# HDMI.net
KiCad netlist of a schematic drawn in Altium Designer
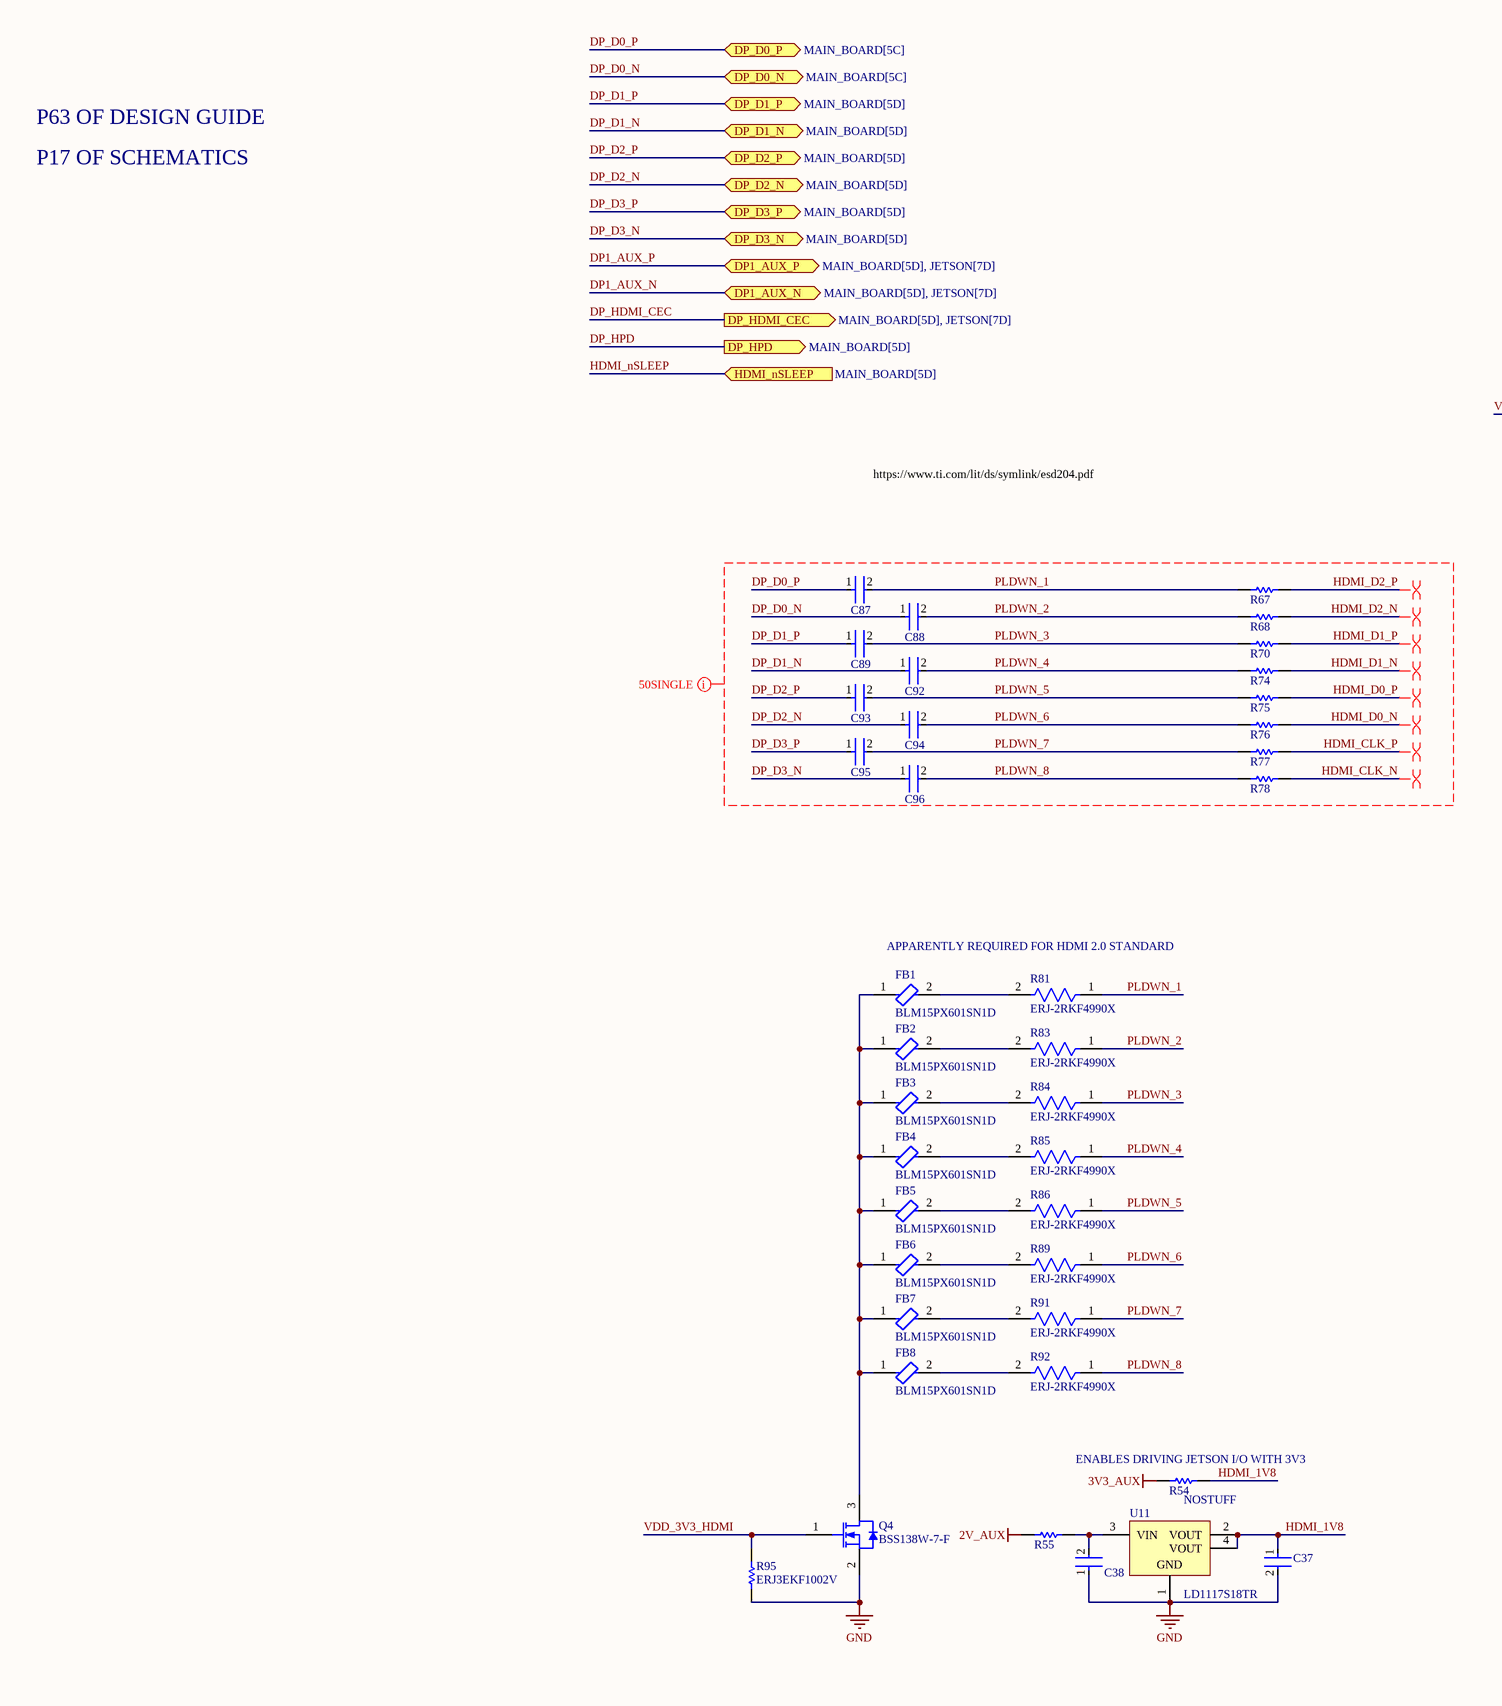
[diagram p0: HDMI.SchDoc, left]
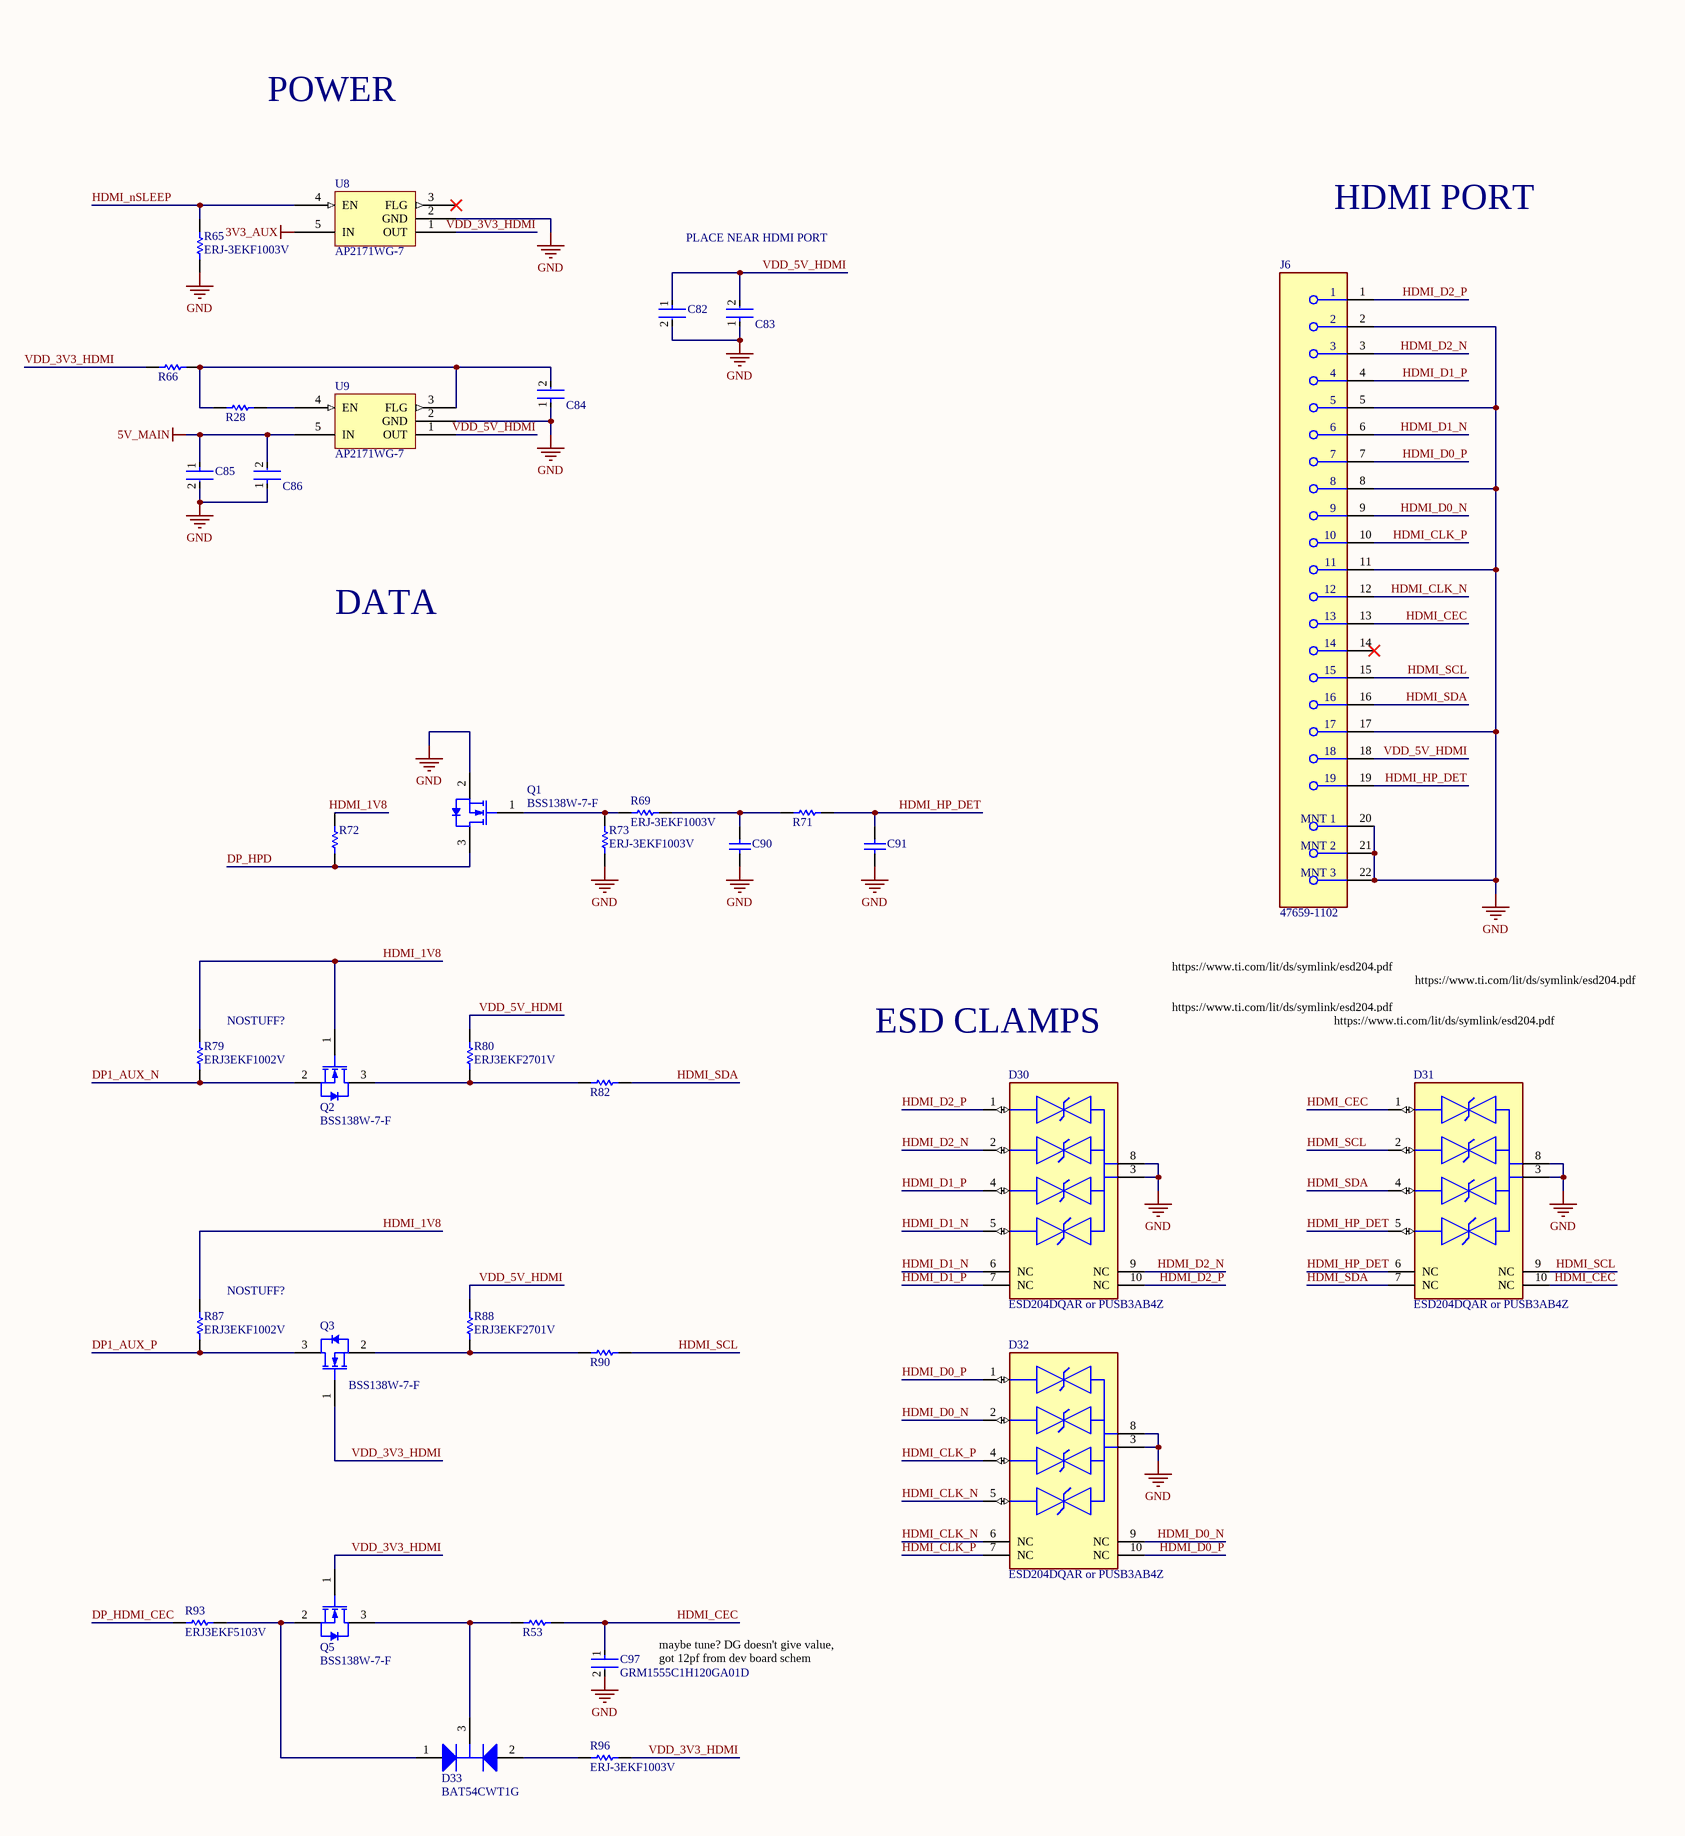
[diagram p1: HDMI.SchDoc, right]

(export (version "E")
  (design (tool "Eeschema 10.0.6"))
  (components
    (comp (ref "C37")
      (value "GRM188R60J106ME47D")
      (footprint "FP-GRM188-0_1-e0_2_0_55-IPC_A")
      (description "Chip Multilayer Ceramic Capacitors for General Purpose, 0603, 10uF, X5R, 15%, 20%, 6.3V")
      (fields (field (name "VOLTAGE") "6.3V") (field (name "TOLERANCE") "20%"))
      (libsource (lib "Altium Content Vault") (part "02cd4be3c70576c341d710602a673aa"))
    )
    (comp (ref "C38")
      (value "C1005X7R1H104K050BB")
      (footprint "FP-C1005-050-0_05-IPC_C")
      (description "Multilayer Ceramic Capacitors 100nF ±10% 50V X7R SMD 0402")
      (fields (field (name "VOLTAGE") "50V") (field (name "TOLERANCE") "10%"))
      (libsource (lib "Altium Content Vault") (part "b4654b650e69147ec39a6b967a45e02"))
    )
    (comp (ref "C82")
      (value "GRM188R60J106ME47D")
      (footprint "FP-GRM188-0_1-e0_2_0_55-IPC_A")
      (description "Chip Multilayer Ceramic Capacitors for General Purpose, 0603, 10uF, X5R, 15%, 20%, 6.3V")
      (fields (field (name "VOLTAGE") "6.3V") (field (name "TOLERANCE") "20%"))
      (libsource (lib "Altium Content Vault") (part "02cd4be3c70576c341d710602a673aa"))
    )
    (comp (ref "C83")
      (value "C1005X7R1H104K050BB")
      (footprint "FP-C1005-050-0_05-IPC_C")
      (description "Multilayer Ceramic Capacitors 100nF ±10% 50V X7R SMD 0402")
      (fields (field (name "VOLTAGE") "50V") (field (name "TOLERANCE") "10%"))
      (libsource (lib "Altium Content Vault") (part "b4654b650e69147ec39a6b967a45e02"))
    )
    (comp (ref "C84")
      (value "C1005X7R1H104K050BB")
      (footprint "FP-C1005-050-0_05-IPC_C")
      (description "Multilayer Ceramic Capacitors 100nF ±10% 50V X7R SMD 0402")
      (fields (field (name "VOLTAGE") "50V") (field (name "TOLERANCE") "10%"))
      (libsource (lib "Altium Content Vault") (part "b4654b650e69147ec39a6b967a45e02"))
    )
    (comp (ref "C85")
      (value "GRM188R60J106ME47D")
      (footprint "FP-GRM188-0_1-e0_2_0_55-IPC_A")
      (description "Chip Multilayer Ceramic Capacitors for General Purpose, 0603, 10uF, X5R, 15%, 20%, 6.3V")
      (fields (field (name "VOLTAGE") "6.3V") (field (name "TOLERANCE") "20%"))
      (libsource (lib "Altium Content Vault") (part "02cd4be3c70576c341d710602a673aa"))
    )
    (comp (ref "C86")
      (value "C1005X7R1H104K050BB")
      (footprint "FP-C1005-050-0_05-IPC_C")
      (description "Multilayer Ceramic Capacitors 100nF ±10% 50V X7R SMD 0402")
      (fields (field (name "VOLTAGE") "50V") (field (name "TOLERANCE") "10%"))
      (libsource (lib "Altium Content Vault") (part "b4654b650e69147ec39a6b967a45e02"))
    )
    (comp (ref "C87")
      (value "C1005X7R1H104K050BB")
      (footprint "FP-C1005-050-0_05-IPC_C")
      (description "Multilayer Ceramic Capacitors 100nF ±10% 50V X7R SMD 0402")
      (fields (field (name "VOLTAGE") "50V") (field (name "TOLERANCE") "10%"))
      (libsource (lib "Altium Content Vault") (part "b4654b650e69147ec39a6b967a45e02"))
    )
    (comp (ref "C88")
      (value "C1005X7R1H104K050BB")
      (footprint "FP-C1005-050-0_05-IPC_C")
      (description "Multilayer Ceramic Capacitors 100nF ±10% 50V X7R SMD 0402")
      (fields (field (name "VOLTAGE") "50V") (field (name "TOLERANCE") "10%"))
      (libsource (lib "Altium Content Vault") (part "b4654b650e69147ec39a6b967a45e02"))
    )
    (comp (ref "C89")
      (value "C1005X7R1H104K050BB")
      (footprint "FP-C1005-050-0_05-IPC_C")
      (description "Multilayer Ceramic Capacitors 100nF ±10% 50V X7R SMD 0402")
      (fields (field (name "VOLTAGE") "50V") (field (name "TOLERANCE") "10%"))
      (libsource (lib "Altium Content Vault") (part "b4654b650e69147ec39a6b967a45e02"))
    )
    (comp (ref "C90")
      (value "C0402C221K5RAC7867")
      (footprint "CAPC1005X60X30NL05T10")
      (fields (field (name "MANUFACTURER") "Kemet"))
      (libsource (lib "Altium Content Vault") (part "CAP"))
    )
    (comp (ref "C91")
      (value "C0402C221K5RAC7867")
      (footprint "CAPC1005X60X30NL05T10")
      (fields (field (name "MANUFACTURER") "Kemet"))
      (libsource (lib "Altium Content Vault") (part "CAP"))
    )
    (comp (ref "C92")
      (value "C1005X7R1H104K050BB")
      (footprint "FP-C1005-050-0_05-IPC_C")
      (description "Multilayer Ceramic Capacitors 100nF ±10% 50V X7R SMD 0402")
      (fields (field (name "VOLTAGE") "50V") (field (name "TOLERANCE") "10%"))
      (libsource (lib "Altium Content Vault") (part "b4654b650e69147ec39a6b967a45e02"))
    )
    (comp (ref "C93")
      (value "C1005X7R1H104K050BB")
      (footprint "FP-C1005-050-0_05-IPC_C")
      (description "Multilayer Ceramic Capacitors 100nF ±10% 50V X7R SMD 0402")
      (fields (field (name "VOLTAGE") "50V") (field (name "TOLERANCE") "10%"))
      (libsource (lib "Altium Content Vault") (part "b4654b650e69147ec39a6b967a45e02"))
    )
    (comp (ref "C94")
      (value "C1005X7R1H104K050BB")
      (footprint "FP-C1005-050-0_05-IPC_C")
      (description "Multilayer Ceramic Capacitors 100nF ±10% 50V X7R SMD 0402")
      (fields (field (name "VOLTAGE") "50V") (field (name "TOLERANCE") "10%"))
      (libsource (lib "Altium Content Vault") (part "b4654b650e69147ec39a6b967a45e02"))
    )
    (comp (ref "C95")
      (value "C1005X7R1H104K050BB")
      (footprint "FP-C1005-050-0_05-IPC_C")
      (description "Multilayer Ceramic Capacitors 100nF ±10% 50V X7R SMD 0402")
      (fields (field (name "VOLTAGE") "50V") (field (name "TOLERANCE") "10%"))
      (libsource (lib "Altium Content Vault") (part "b4654b650e69147ec39a6b967a45e02"))
    )
    (comp (ref "C96")
      (value "C1005X7R1H104K050BB")
      (footprint "FP-C1005-050-0_05-IPC_C")
      (description "Multilayer Ceramic Capacitors 100nF ±10% 50V X7R SMD 0402")
      (fields (field (name "VOLTAGE") "50V") (field (name "TOLERANCE") "10%"))
      (libsource (lib "Altium Content Vault") (part "b4654b650e69147ec39a6b967a45e02"))
    )
    (comp (ref "C97")
      (value "GRM1555C1H120GA01D")
      (footprint "FP-GRM155-0_05-MFG")
      (description "CAP CER 12PF 50V C0G/NP0 0402")
      (fields (field (name "TOLERANCE") "2%") (field (name "VOLTAGE") "50V"))
      (libsource (lib "Altium Content Vault") (part "b4654b650e69147ec39a6b967a45e02"))
    )
    (comp (ref "D30")
      (value "ESD204DQAR or PUSB3AB4Z")
      (footprint "FP-DQA0010A-MFG")
      (description "4-CHANNEL LOW-CAPACITANCE SURGE")
      (fields
        (field (name "MANUFACTURER") "Texas Instruments")
        (field (name "OCTOPART") "https://octopart.com/esd204dqar-texas+instruments-89917476")
      )
      (libsource (lib "Altium Content Vault") (part "1465e58c1818c7767b55926832f0bf5"))
    )
    (comp (ref "D31")
      (value "ESD204DQAR or PUSB3AB4Z")
      (footprint "FP-DQA0010A-MFG")
      (description "4-CHANNEL LOW-CAPACITANCE SURGE")
      (fields
        (field (name "MANUFACTURER") "Texas Instruments")
        (field (name "OCTOPART") "https://octopart.com/esd204dqar-texas+instruments-89917476")
      )
      (libsource (lib "Altium Content Vault") (part "1465e58c1818c7767b55926832f0bf5"))
    )
    (comp (ref "D32")
      (value "ESD204DQAR or PUSB3AB4Z")
      (footprint "FP-DQA0010A-MFG")
      (description "4-CHANNEL LOW-CAPACITANCE SURGE")
      (fields
        (field (name "MANUFACTURER") "Texas Instruments")
        (field (name "OCTOPART") "https://octopart.com/esd204dqar-texas+instruments-89917476")
      )
      (libsource (lib "Altium Content Vault") (part "1465e58c1818c7767b55926832f0bf5"))
    )
    (comp (ref "D33")
      (value "BAT54CWT1G")
      (footprint "ONSC-SOT-323-3-419-04_V")
      (description "Dual Series Cathode Schottky Barrier Diodes, 3-Pin SOT-323, Pb-Free, Tape and Reel")
      (fields (field (name "MANUFACTURER") "On Semiconductor"))
      (libsource (lib "Altium Content Vault") (part "ONSC-D-A1A2K3-3"))
    )
    (comp (ref "FB1")
      (value "BLM15PX601SN1D")
      (footprint "FP-BLM15-0_05-MFG")
      (description "Chip Ferrite Bead, 0402, 600Ω @ 100MHz, 0.23Ω, 25%, 900mA")
      (fields (field (name "TOLERANCE") "25%"))
      (libsource (lib "Altium Content Vault") (part "5f30dd21d616792df468990f7003faa"))
    )
    (comp (ref "FB2")
      (value "BLM15PX601SN1D")
      (footprint "FP-BLM15-0_05-MFG")
      (description "Chip Ferrite Bead, 0402, 600Ω @ 100MHz, 0.23Ω, 25%, 900mA")
      (fields (field (name "TOLERANCE") "25%"))
      (libsource (lib "Altium Content Vault") (part "5f30dd21d616792df468990f7003faa"))
    )
    (comp (ref "FB3")
      (value "BLM15PX601SN1D")
      (footprint "FP-BLM15-0_05-MFG")
      (description "Chip Ferrite Bead, 0402, 600Ω @ 100MHz, 0.23Ω, 25%, 900mA")
      (fields (field (name "TOLERANCE") "25%"))
      (libsource (lib "Altium Content Vault") (part "5f30dd21d616792df468990f7003faa"))
    )
    (comp (ref "FB4")
      (value "BLM15PX601SN1D")
      (footprint "FP-BLM15-0_05-MFG")
      (description "Chip Ferrite Bead, 0402, 600Ω @ 100MHz, 0.23Ω, 25%, 900mA")
      (fields (field (name "TOLERANCE") "25%"))
      (libsource (lib "Altium Content Vault") (part "5f30dd21d616792df468990f7003faa"))
    )
    (comp (ref "FB5")
      (value "BLM15PX601SN1D")
      (footprint "FP-BLM15-0_05-MFG")
      (description "Chip Ferrite Bead, 0402, 600Ω @ 100MHz, 0.23Ω, 25%, 900mA")
      (fields (field (name "TOLERANCE") "25%"))
      (libsource (lib "Altium Content Vault") (part "5f30dd21d616792df468990f7003faa"))
    )
    (comp (ref "FB6")
      (value "BLM15PX601SN1D")
      (footprint "FP-BLM15-0_05-MFG")
      (description "Chip Ferrite Bead, 0402, 600Ω @ 100MHz, 0.23Ω, 25%, 900mA")
      (fields (field (name "TOLERANCE") "25%"))
      (libsource (lib "Altium Content Vault") (part "5f30dd21d616792df468990f7003faa"))
    )
    (comp (ref "FB7")
      (value "BLM15PX601SN1D")
      (footprint "FP-BLM15-0_05-MFG")
      (description "Chip Ferrite Bead, 0402, 600Ω @ 100MHz, 0.23Ω, 25%, 900mA")
      (fields (field (name "TOLERANCE") "25%"))
      (libsource (lib "Altium Content Vault") (part "5f30dd21d616792df468990f7003faa"))
    )
    (comp (ref "FB8")
      (value "BLM15PX601SN1D")
      (footprint "FP-BLM15-0_05-MFG")
      (description "Chip Ferrite Bead, 0402, 600Ω @ 100MHz, 0.23Ω, 25%, 900mA")
      (fields (field (name "TOLERANCE") "25%"))
      (libsource (lib "Altium Content Vault") (part "5f30dd21d616792df468990f7003faa"))
    )
    (comp (ref "J6")
      (value "47659-1102")
      (footprint "FP-47659-1102-MFG")
      (description "HDMI REC.VERTICAL SMT TYPE W/HEI")
      (libsource (lib "Altium Content Vault") (part "60e05bcc1364a128ef07df4509dd673"))
    )
    (comp (ref "Q1")
      (value "BSS138W-7-F")
      (footprint "DIOD-SOT323-3_V")
      (fields (field (name "MANUFACTURER") "DiodesIncorporated"))
      (libsource (lib "Altium Content Vault") (part "NEMOS-GSD-3"))
    )
    (comp (ref "Q2")
      (value "BSS138W-7-F")
      (footprint "DIOD-SOT323-3_V")
      (fields (field (name "MANUFACTURER") "DiodesIncorporated"))
      (libsource (lib "Altium Content Vault") (part "NEMOS-GSD-3"))
    )
    (comp (ref "Q3")
      (value "BSS138W-7-F")
      (footprint "DIOD-SOT323-3_V")
      (fields (field (name "MANUFACTURER") "DiodesIncorporated"))
      (libsource (lib "Altium Content Vault") (part "NEMOS-GSD-3"))
    )
    (comp (ref "Q4")
      (value "BSS138W-7-F")
      (footprint "DIOD-SOT323-3_V")
      (fields (field (name "MANUFACTURER") "DiodesIncorporated"))
      (libsource (lib "Altium Content Vault") (part "NEMOS-GSD-3"))
    )
    (comp (ref "Q5")
      (value "BSS138W-7-F")
      (footprint "DIOD-SOT323-3_V")
      (fields (field (name "MANUFACTURER") "DiodesIncorporated"))
      (libsource (lib "Altium Content Vault") (part "NEMOS-GSD-3"))
    )
    (comp (ref "R28")
      (value "0402 JUMPER 0 OHM")
      (footprint "RESC1005X40X25NL05T05")
      (description "READ THE NAME")
      (libsource (lib "uORocketry Hardware") (part "RES"))
    )
    (comp (ref "R53")
      (value "0402 JUMPER 0 OHM")
      (footprint "RESC1005X40X25NL05T05")
      (description "READ THE NAME")
      (libsource (lib "uORocketry Hardware") (part "RES"))
    )
    (comp (ref "R54")
      (value "0402 JUMPER 0 OHM")
      (footprint "RESC1005X40X25NL05T05")
      (description "READ THE NAME")
      (libsource (lib "uORocketry Hardware") (part "RES"))
    )
    (comp (ref "R55")
      (value "0402 JUMPER 0 OHM")
      (footprint "RESC1005X40X25NL05T05")
      (description "READ THE NAME")
      (libsource (lib "uORocketry Hardware") (part "RES"))
    )
    (comp (ref "R65")
      (value "ERJ-3EKF1003V")
      (footprint "RESC1608X55X30ML15T15")
      (fields (field (name "MANUFACTURER") "Panasonic"))
      (libsource (lib "Altium Content Vault") (part "RES"))
    )
    (comp (ref "R66")
      (value "ERJ3EKF1002V")
      (footprint "RESC1609X55X30LL15T15")
      (description "Chip Resistor, 10 KOhm, +/- 1%, 0.1 W, -55 to 155 degC, 0603 (1608 Metric), RoHS, Tape and Reel")
      (fields (field (name "TOLERANCE") "1%") (field (name "MANUFACTURER") "Panasonic"))
      (libsource (lib "Altium Content Vault") (part "RES-2"))
    )
    (comp (ref "R67")
      (value "0402 JUMPER 0 OHM")
      (footprint "RESC1005X40X25NL05T05")
      (description "READ THE NAME")
      (libsource (lib "uORocketry Hardware") (part "RES"))
    )
    (comp (ref "R68")
      (value "0402 JUMPER 0 OHM")
      (footprint "RESC1005X40X25NL05T05")
      (description "READ THE NAME")
      (libsource (lib "uORocketry Hardware") (part "RES"))
    )
    (comp (ref "R69")
      (value "ERJ-3EKF1003V")
      (footprint "RESC1608X55X30ML15T15")
      (fields (field (name "MANUFACTURER") "Panasonic"))
      (libsource (lib "Altium Content Vault") (part "RES"))
    )
    (comp (ref "R70")
      (value "0402 JUMPER 0 OHM")
      (footprint "RESC1005X40X25NL05T05")
      (description "READ THE NAME")
      (libsource (lib "uORocketry Hardware") (part "RES"))
    )
    (comp (ref "R71")
      (value "0402 JUMPER 0 OHM")
      (footprint "RESC1005X40X25NL05T05")
      (description "READ THE NAME")
      (libsource (lib "uORocketry Hardware") (part "RES"))
    )
    (comp (ref "R72")
      (value "ERJ3EKF1002V")
      (footprint "RESC1609X55X30LL15T15")
      (description "Chip Resistor, 10 KOhm, +/- 1%, 0.1 W, -55 to 155 degC, 0603 (1608 Metric), RoHS, Tape and Reel")
      (fields (field (name "TOLERANCE") "1%") (field (name "MANUFACTURER") "Panasonic"))
      (libsource (lib "Altium Content Vault") (part "RES-2"))
    )
    (comp (ref "R73")
      (value "ERJ-3EKF1003V")
      (footprint "RESC1608X55X30ML15T15")
      (fields (field (name "MANUFACTURER") "Panasonic"))
      (libsource (lib "Altium Content Vault") (part "RES"))
    )
    (comp (ref "R74")
      (value "0402 JUMPER 0 OHM")
      (footprint "RESC1005X40X25NL05T05")
      (description "READ THE NAME")
      (libsource (lib "uORocketry Hardware") (part "RES"))
    )
    (comp (ref "R75")
      (value "0402 JUMPER 0 OHM")
      (footprint "RESC1005X40X25NL05T05")
      (description "READ THE NAME")
      (libsource (lib "uORocketry Hardware") (part "RES"))
    )
    (comp (ref "R76")
      (value "0402 JUMPER 0 OHM")
      (footprint "RESC1005X40X25NL05T05")
      (description "READ THE NAME")
      (libsource (lib "uORocketry Hardware") (part "RES"))
    )
    (comp (ref "R77")
      (value "0402 JUMPER 0 OHM")
      (footprint "RESC1005X40X25NL05T05")
      (description "READ THE NAME")
      (libsource (lib "uORocketry Hardware") (part "RES"))
    )
    (comp (ref "R78")
      (value "0402 JUMPER 0 OHM")
      (footprint "RESC1005X40X25NL05T05")
      (description "READ THE NAME")
      (libsource (lib "uORocketry Hardware") (part "RES"))
    )
    (comp (ref "R79")
      (value "ERJ3EKF1002V")
      (footprint "RESC1609X55X30LL15T15")
      (description "Chip Resistor, 10 KOhm, +/- 1%, 0.1 W, -55 to 155 degC, 0603 (1608 Metric), RoHS, Tape and Reel")
      (fields (field (name "TOLERANCE") "1%") (field (name "MANUFACTURER") "Panasonic"))
      (libsource (lib "Altium Content Vault") (part "RES-2"))
    )
    (comp (ref "R80")
      (value "ERJ3EKF2701V")
      (footprint "RESC1608X55X30LL15T15")
      (fields (field (name "MANUFACTURER") "Panasonic"))
      (libsource (lib "Altium Content Vault") (part "RES"))
    )
    (comp (ref "R81")
      (value "ERJ-2RKF4990X")
      (footprint "FP-ERJ2RK-MFG")
      (description "RES SMD 499 OHM 1% 1/10W 0402")
      (fields (field (name "TOLERANCE") "1%"))
      (libsource (lib "Altium Content Vault") (part "1029c3af85768c4190bb7ad29bc67b5"))
    )
    (comp (ref "R82")
      (value "0402 JUMPER 0 OHM")
      (footprint "RESC1005X40X25NL05T05")
      (description "READ THE NAME")
      (libsource (lib "uORocketry Hardware") (part "RES"))
    )
    (comp (ref "R83")
      (value "ERJ-2RKF4990X")
      (footprint "FP-ERJ2RK-MFG")
      (description "RES SMD 499 OHM 1% 1/10W 0402")
      (fields (field (name "TOLERANCE") "1%"))
      (libsource (lib "Altium Content Vault") (part "1029c3af85768c4190bb7ad29bc67b5"))
    )
    (comp (ref "R84")
      (value "ERJ-2RKF4990X")
      (footprint "FP-ERJ2RK-MFG")
      (description "RES SMD 499 OHM 1% 1/10W 0402")
      (fields (field (name "TOLERANCE") "1%"))
      (libsource (lib "Altium Content Vault") (part "1029c3af85768c4190bb7ad29bc67b5"))
    )
    (comp (ref "R85")
      (value "ERJ-2RKF4990X")
      (footprint "FP-ERJ2RK-MFG")
      (description "RES SMD 499 OHM 1% 1/10W 0402")
      (fields (field (name "TOLERANCE") "1%"))
      (libsource (lib "Altium Content Vault") (part "1029c3af85768c4190bb7ad29bc67b5"))
    )
    (comp (ref "R86")
      (value "ERJ-2RKF4990X")
      (footprint "FP-ERJ2RK-MFG")
      (description "RES SMD 499 OHM 1% 1/10W 0402")
      (fields (field (name "TOLERANCE") "1%"))
      (libsource (lib "Altium Content Vault") (part "1029c3af85768c4190bb7ad29bc67b5"))
    )
    (comp (ref "R87")
      (value "ERJ3EKF1002V")
      (footprint "RESC1609X55X30LL15T15")
      (description "Chip Resistor, 10 KOhm, +/- 1%, 0.1 W, -55 to 155 degC, 0603 (1608 Metric), RoHS, Tape and Reel")
      (fields (field (name "TOLERANCE") "1%") (field (name "MANUFACTURER") "Panasonic"))
      (libsource (lib "Altium Content Vault") (part "RES-2"))
    )
    (comp (ref "R88")
      (value "ERJ3EKF2701V")
      (footprint "RESC1608X55X30LL15T15")
      (fields (field (name "MANUFACTURER") "Panasonic"))
      (libsource (lib "Altium Content Vault") (part "RES"))
    )
    (comp (ref "R89")
      (value "ERJ-2RKF4990X")
      (footprint "FP-ERJ2RK-MFG")
      (description "RES SMD 499 OHM 1% 1/10W 0402")
      (fields (field (name "TOLERANCE") "1%"))
      (libsource (lib "Altium Content Vault") (part "1029c3af85768c4190bb7ad29bc67b5"))
    )
    (comp (ref "R90")
      (value "0402 JUMPER 0 OHM")
      (footprint "RESC1005X40X25NL05T05")
      (description "READ THE NAME")
      (libsource (lib "uORocketry Hardware") (part "RES"))
    )
    (comp (ref "R91")
      (value "ERJ-2RKF4990X")
      (footprint "FP-ERJ2RK-MFG")
      (description "RES SMD 499 OHM 1% 1/10W 0402")
      (fields (field (name "TOLERANCE") "1%"))
      (libsource (lib "Altium Content Vault") (part "1029c3af85768c4190bb7ad29bc67b5"))
    )
    (comp (ref "R92")
      (value "ERJ-2RKF4990X")
      (footprint "FP-ERJ2RK-MFG")
      (description "RES SMD 499 OHM 1% 1/10W 0402")
      (fields (field (name "TOLERANCE") "1%"))
      (libsource (lib "Altium Content Vault") (part "1029c3af85768c4190bb7ad29bc67b5"))
    )
    (comp (ref "R93")
      (value "ERJ3EKF5103V")
      (footprint "RESC1608X55X30LL15T15")
      (fields (field (name "MANUFACTURER") "Panasonic"))
      (libsource (lib "Altium Content Vault") (part "RES"))
    )
    (comp (ref "R95")
      (value "ERJ3EKF1002V")
      (footprint "RESC1609X55X30LL15T15")
      (description "Chip Resistor, 10 KOhm, +/- 1%, 0.1 W, -55 to 155 degC, 0603 (1608 Metric), RoHS, Tape and Reel")
      (fields (field (name "TOLERANCE") "1%") (field (name "MANUFACTURER") "Panasonic"))
      (libsource (lib "Altium Content Vault") (part "RES-2"))
    )
    (comp (ref "R96")
      (value "ERJ-3EKF1003V")
      (footprint "RESC1608X55X30ML15T15")
      (fields (field (name "MANUFACTURER") "Panasonic"))
      (libsource (lib "Altium Content Vault") (part "RES"))
    )
    (comp (ref "U8")
      (value "AP2171WG-7")
      (footprint "SOT95P285X130-5N")
      (description "IC PWR SW USB 1CH 1A SOT-25-5")
      (libsource (lib "uORocketry Hardware") (part "AP2171WG-7"))
    )
    (comp (ref "U9")
      (value "AP2171WG-7")
      (footprint "SOT95P285X130-5N")
      (description "IC PWR SW USB 1CH 1A SOT-25-5")
      (libsource (lib "uORocketry Hardware") (part "AP2171WG-7"))
    )
    (comp (ref "U11")
      (value "LD1117S18TR")
      (footprint "SOT-223_M")
      (description "Fixed Low Drop Positive Voltage Regulator, 1.8V, 4-Pin SOT-223, Tape and Reel")
      (libsource (lib "Altium Content Vault") (part "PM-REG-LD1117-SOT4"))
    )
  )
  (nets
    (net (code "1") (name "/DP1_AUX_N") (class "Default")
      (node (ref "Q2") (pin "2") (pinfunction "S_2") (pintype "passive"))
      (node (ref "R79") (pin "1") (pinfunction "1_1") (pintype "passive"))
    )
    (net (code "2") (name "/DP1_AUX_P") (class "Default")
      (node (ref "Q3") (pin "3") (pinfunction "D_3") (pintype "passive"))
      (node (ref "R87") (pin "1") (pinfunction "1_1") (pintype "passive"))
    )
    (net (code "3") (name "/DP_D0_N") (class "Default")
      (node (ref "C88") (pin "1") (pinfunction "1_1") (pintype "passive"))
    )
    (net (code "4") (name "/DP_D0_P") (class "Default")
      (node (ref "C87") (pin "1") (pinfunction "1_1") (pintype "passive"))
    )
    (net (code "5") (name "/DP_D1_N") (class "Default")
      (node (ref "C92") (pin "1") (pinfunction "1_1") (pintype "passive"))
    )
    (net (code "6") (name "/DP_D1_P") (class "Default")
      (node (ref "C89") (pin "1") (pinfunction "1_1") (pintype "passive"))
    )
    (net (code "7") (name "/DP_D2_N") (class "Default")
      (node (ref "C94") (pin "1") (pinfunction "1_1") (pintype "passive"))
    )
    (net (code "8") (name "/DP_D2_P") (class "Default")
      (node (ref "C93") (pin "1") (pinfunction "1_1") (pintype "passive"))
    )
    (net (code "9") (name "/DP_D3_N") (class "Default")
      (node (ref "C96") (pin "1") (pinfunction "1_1") (pintype "passive"))
    )
    (net (code "10") (name "/DP_D3_P") (class "Default")
      (node (ref "C95") (pin "1") (pinfunction "1_1") (pintype "passive"))
    )
    (net (code "11") (name "/DP_HDMI_CEC") (class "Default")
      (node (ref "R93") (pin "1") (pinfunction "1_1") (pintype "passive"))
    )
    (net (code "12") (name "/DP_HPD") (class "Default")
      (node (ref "Q1") (pin "3") (pinfunction "D_3") (pintype "passive"))
      (node (ref "R72") (pin "1") (pinfunction "1_1") (pintype "passive"))
    )
    (net (code "13") (name "/HDMI_1V8") (class "Default")
      (node (ref "C37") (pin "1") (pinfunction "1_1") (pintype "passive"))
      (node (ref "Q2") (pin "1") (pinfunction "G_1") (pintype "passive"))
      (node (ref "R54") (pin "2") (pinfunction "2_2") (pintype "passive"))
      (node (ref "R72") (pin "2") (pinfunction "2_2") (pintype "passive"))
      (node (ref "R79") (pin "2") (pinfunction "2_2") (pintype "passive"))
      (node (ref "R87") (pin "2") (pinfunction "2_2") (pintype "passive"))
      (node (ref "U11") (pin "2") (pinfunction "VOUT_2") (pintype "power_in"))
      (node (ref "U11") (pin "4") (pinfunction "VOUT_4") (pintype "power_in"))
    )
    (net (code "14") (name "/HDMI_CEC") (class "Default")
      (node (ref "C97") (pin "1") (pinfunction "1_1") (pintype "passive"))
      (node (ref "D31") (pin "1") (pinfunction "IO1_1") (pintype "bidirectional"))
      (node (ref "D31") (pin "10") (pinfunction "NC_10") (pintype "passive"))
      (node (ref "J6") (pin "13") (pinfunction "13_13") (pintype "passive"))
      (node (ref "R53") (pin "2") (pinfunction "2_2") (pintype "passive"))
    )
    (net (code "15") (name "/HDMI_CLK_N") (class "Default")
      (node (ref "D32") (pin "5") (pinfunction "IO4_5") (pintype "bidirectional"))
      (node (ref "D32") (pin "6") (pinfunction "NC_6") (pintype "passive"))
      (node (ref "J6") (pin "12") (pinfunction "12_12") (pintype "passive"))
      (node (ref "R78") (pin "2") (pinfunction "2_2") (pintype "passive"))
    )
    (net (code "16") (name "/HDMI_CLK_P") (class "Default")
      (node (ref "D32") (pin "4") (pinfunction "IO3_4") (pintype "bidirectional"))
      (node (ref "D32") (pin "7") (pinfunction "NC_7") (pintype "passive"))
      (node (ref "J6") (pin "10") (pinfunction "10_10") (pintype "passive"))
      (node (ref "R77") (pin "2") (pinfunction "2_2") (pintype "passive"))
    )
    (net (code "17") (name "/HDMI_D0_N") (class "Default")
      (node (ref "D32") (pin "2") (pinfunction "IO2_2") (pintype "bidirectional"))
      (node (ref "D32") (pin "9") (pinfunction "NC_9") (pintype "passive"))
      (node (ref "J6") (pin "9") (pinfunction "9_9") (pintype "passive"))
      (node (ref "R76") (pin "2") (pinfunction "2_2") (pintype "passive"))
    )
    (net (code "18") (name "/HDMI_D0_P") (class "Default")
      (node (ref "D32") (pin "1") (pinfunction "IO1_1") (pintype "bidirectional"))
      (node (ref "D32") (pin "10") (pinfunction "NC_10") (pintype "passive"))
      (node (ref "J6") (pin "7") (pinfunction "7_7") (pintype "passive"))
      (node (ref "R75") (pin "2") (pinfunction "2_2") (pintype "passive"))
    )
    (net (code "19") (name "/HDMI_D1_N") (class "Default")
      (node (ref "D30") (pin "5") (pinfunction "IO4_5") (pintype "bidirectional"))
      (node (ref "D30") (pin "6") (pinfunction "NC_6") (pintype "passive"))
      (node (ref "J6") (pin "6") (pinfunction "6_6") (pintype "passive"))
      (node (ref "R74") (pin "2") (pinfunction "2_2") (pintype "passive"))
    )
    (net (code "20") (name "/HDMI_D1_P") (class "Default")
      (node (ref "D30") (pin "4") (pinfunction "IO3_4") (pintype "bidirectional"))
      (node (ref "D30") (pin "7") (pinfunction "NC_7") (pintype "passive"))
      (node (ref "J6") (pin "4") (pinfunction "4_4") (pintype "passive"))
      (node (ref "R70") (pin "2") (pinfunction "2_2") (pintype "passive"))
    )
    (net (code "21") (name "/HDMI_D2_N") (class "Default")
      (node (ref "D30") (pin "2") (pinfunction "IO2_2") (pintype "bidirectional"))
      (node (ref "D30") (pin "9") (pinfunction "NC_9") (pintype "passive"))
      (node (ref "J6") (pin "3") (pinfunction "3_3") (pintype "passive"))
      (node (ref "R68") (pin "2") (pinfunction "2_2") (pintype "passive"))
    )
    (net (code "22") (name "/HDMI_D2_P") (class "Default")
      (node (ref "D30") (pin "1") (pinfunction "IO1_1") (pintype "bidirectional"))
      (node (ref "D30") (pin "10") (pinfunction "NC_10") (pintype "passive"))
      (node (ref "J6") (pin "1") (pinfunction "1_1") (pintype "passive"))
      (node (ref "R67") (pin "2") (pinfunction "2_2") (pintype "passive"))
    )
    (net (code "23") (name "/HDMI_HP_DET") (class "Default")
      (node (ref "C91") (pin "2") (pinfunction "2_2") (pintype "passive"))
      (node (ref "D31") (pin "5") (pinfunction "IO4_5") (pintype "bidirectional"))
      (node (ref "D31") (pin "6") (pinfunction "NC_6") (pintype "passive"))
      (node (ref "J6") (pin "19") (pinfunction "19_19") (pintype "passive"))
      (node (ref "R71") (pin "2") (pinfunction "2_2") (pintype "passive"))
    )
    (net (code "24") (name "/HDMI_SCL") (class "Default")
      (node (ref "D31") (pin "2") (pinfunction "IO2_2") (pintype "bidirectional"))
      (node (ref "D31") (pin "9") (pinfunction "NC_9") (pintype "passive"))
      (node (ref "J6") (pin "15") (pinfunction "15_15") (pintype "passive"))
      (node (ref "R90") (pin "2") (pinfunction "2_2") (pintype "passive"))
    )
    (net (code "25") (name "/HDMI_SDA") (class "Default")
      (node (ref "D31") (pin "4") (pinfunction "IO3_4") (pintype "bidirectional"))
      (node (ref "D31") (pin "7") (pinfunction "NC_7") (pintype "passive"))
      (node (ref "J6") (pin "16") (pinfunction "16_16") (pintype "passive"))
      (node (ref "R82") (pin "2") (pinfunction "2_2") (pintype "passive"))
    )
    (net (code "26") (name "/HDMI_nSLEEP") (class "Default")
      (node (ref "R65") (pin "2") (pinfunction "2_2") (pintype "passive"))
      (node (ref "U8") (pin "4") (pinfunction "EN_4") (pintype "input"))
    )
    (net (code "27") (name "/PLDWN_1") (class "Default")
      (node (ref "C87") (pin "2") (pinfunction "2_2") (pintype "passive"))
      (node (ref "R67") (pin "1") (pinfunction "1_1") (pintype "passive"))
      (node (ref "R81") (pin "1") (pinfunction "1_1") (pintype "passive"))
    )
    (net (code "28") (name "/PLDWN_2") (class "Default")
      (node (ref "C88") (pin "2") (pinfunction "2_2") (pintype "passive"))
      (node (ref "R68") (pin "1") (pinfunction "1_1") (pintype "passive"))
      (node (ref "R83") (pin "1") (pinfunction "1_1") (pintype "passive"))
    )
    (net (code "29") (name "/PLDWN_3") (class "Default")
      (node (ref "C89") (pin "2") (pinfunction "2_2") (pintype "passive"))
      (node (ref "R70") (pin "1") (pinfunction "1_1") (pintype "passive"))
      (node (ref "R84") (pin "1") (pinfunction "1_1") (pintype "passive"))
    )
    (net (code "30") (name "/PLDWN_4") (class "Default")
      (node (ref "C92") (pin "2") (pinfunction "2_2") (pintype "passive"))
      (node (ref "R74") (pin "1") (pinfunction "1_1") (pintype "passive"))
      (node (ref "R85") (pin "1") (pinfunction "1_1") (pintype "passive"))
    )
    (net (code "31") (name "/PLDWN_5") (class "Default")
      (node (ref "C93") (pin "2") (pinfunction "2_2") (pintype "passive"))
      (node (ref "R75") (pin "1") (pinfunction "1_1") (pintype "passive"))
      (node (ref "R86") (pin "1") (pinfunction "1_1") (pintype "passive"))
    )
    (net (code "32") (name "/PLDWN_6") (class "Default")
      (node (ref "C94") (pin "2") (pinfunction "2_2") (pintype "passive"))
      (node (ref "R76") (pin "1") (pinfunction "1_1") (pintype "passive"))
      (node (ref "R89") (pin "1") (pinfunction "1_1") (pintype "passive"))
    )
    (net (code "33") (name "/PLDWN_7") (class "Default")
      (node (ref "C95") (pin "2") (pinfunction "2_2") (pintype "passive"))
      (node (ref "R77") (pin "1") (pinfunction "1_1") (pintype "passive"))
      (node (ref "R91") (pin "1") (pinfunction "1_1") (pintype "passive"))
    )
    (net (code "34") (name "/PLDWN_8") (class "Default")
      (node (ref "C96") (pin "2") (pinfunction "2_2") (pintype "passive"))
      (node (ref "R78") (pin "1") (pinfunction "1_1") (pintype "passive"))
      (node (ref "R92") (pin "1") (pinfunction "1_1") (pintype "passive"))
    )
    (net (code "35") (name "/VDD_3V3_HDMI") (class "Default")
      (node (ref "Q3") (pin "1") (pinfunction "G_1") (pintype "passive"))
      (node (ref "Q4") (pin "1") (pinfunction "G_1") (pintype "passive"))
      (node (ref "Q5") (pin "1") (pinfunction "G_1") (pintype "passive"))
      (node (ref "R66") (pin "2") (pinfunction "2_2") (pintype "passive"))
      (node (ref "R95") (pin "2") (pinfunction "2_2") (pintype "passive"))
      (node (ref "R96") (pin "2") (pinfunction "2_2") (pintype "passive"))
      (node (ref "U8") (pin "1") (pinfunction "OUT_1") (pintype "passive"))
    )
    (net (code "36") (name "/VDD_5V_HDMI") (class "Default")
      (node (ref "C82") (pin "1") (pinfunction "1_1") (pintype "passive"))
      (node (ref "C83") (pin "2") (pinfunction "2_2") (pintype "passive"))
      (node (ref "J6") (pin "18") (pinfunction "18_18") (pintype "passive"))
      (node (ref "R80") (pin "2") (pinfunction "2_2") (pintype "passive"))
      (node (ref "R88") (pin "2") (pinfunction "2_2") (pintype "passive"))
      (node (ref "U9") (pin "1") (pinfunction "OUT_1") (pintype "passive"))
    )
    (net (code "37") (name "2V_AUX") (class "Default")
      (node (ref "R55") (pin "1") (pinfunction "1_1") (pintype "passive"))
    )
    (net (code "38") (name "3V3_AUX") (class "Default")
      (node (ref "R54") (pin "1") (pinfunction "1_1") (pintype "passive"))
      (node (ref "U8") (pin "5") (pinfunction "IN_5") (pintype "passive"))
    )
    (net (code "39") (name "5V_MAIN") (class "Default")
      (node (ref "C85") (pin "1") (pinfunction "1_1") (pintype "passive"))
      (node (ref "C86") (pin "2") (pinfunction "2_2") (pintype "passive"))
      (node (ref "U9") (pin "5") (pinfunction "IN_5") (pintype "passive"))
    )
    (net (code "40") (name "GND") (class "Default")
      (node (ref "C37") (pin "2") (pinfunction "2_2") (pintype "passive"))
      (node (ref "C38") (pin "1") (pinfunction "1_1") (pintype "passive"))
      (node (ref "C82") (pin "2") (pinfunction "2_2") (pintype "passive"))
      (node (ref "C83") (pin "1") (pinfunction "1_1") (pintype "passive"))
      (node (ref "C84") (pin "1") (pinfunction "1_1") (pintype "passive"))
      (node (ref "C85") (pin "2") (pinfunction "2_2") (pintype "passive"))
      (node (ref "C86") (pin "1") (pinfunction "1_1") (pintype "passive"))
      (node (ref "C90") (pin "1") (pinfunction "1_1") (pintype "passive"))
      (node (ref "C91") (pin "1") (pinfunction "1_1") (pintype "passive"))
      (node (ref "C97") (pin "2") (pinfunction "2_2") (pintype "passive"))
      (node (ref "D30") (pin "3") (pinfunction "GND_3") (pintype "power_in"))
      (node (ref "D30") (pin "8") (pinfunction "GND_8") (pintype "power_in"))
      (node (ref "D31") (pin "3") (pinfunction "GND_3") (pintype "power_in"))
      (node (ref "D31") (pin "8") (pinfunction "GND_8") (pintype "power_in"))
      (node (ref "D32") (pin "3") (pinfunction "GND_3") (pintype "power_in"))
      (node (ref "D32") (pin "8") (pinfunction "GND_8") (pintype "power_in"))
      (node (ref "J6") (pin "11") (pinfunction "11_11") (pintype "passive"))
      (node (ref "J6") (pin "17") (pinfunction "17_17") (pintype "passive"))
      (node (ref "J6") (pin "2") (pinfunction "2_2") (pintype "passive"))
      (node (ref "J6") (pin "20") (pinfunction "MNT_1_20") (pintype "passive"))
      (node (ref "J6") (pin "21") (pinfunction "MNT_2_21") (pintype "passive"))
      (node (ref "J6") (pin "22") (pinfunction "MNT_3_22") (pintype "passive"))
      (node (ref "J6") (pin "5") (pinfunction "5_5") (pintype "passive"))
      (node (ref "J6") (pin "8") (pinfunction "8_8") (pintype "passive"))
      (node (ref "Q1") (pin "2") (pinfunction "S_2") (pintype "passive"))
      (node (ref "Q4") (pin "2") (pinfunction "S_2") (pintype "passive"))
      (node (ref "R65") (pin "1") (pinfunction "1_1") (pintype "passive"))
      (node (ref "R73") (pin "1") (pinfunction "1_1") (pintype "passive"))
      (node (ref "R95") (pin "1") (pinfunction "1_1") (pintype "passive"))
      (node (ref "U11") (pin "1") (pinfunction "GND_1") (pintype "power_in"))
      (node (ref "U8") (pin "2") (pinfunction "GND_2") (pintype "passive"))
      (node (ref "U9") (pin "2") (pinfunction "GND_2") (pintype "passive"))
    )
    (net (code "41") (name "Net-(C90-Pad2)") (class "Default")
      (node (ref "C90") (pin "2") (pinfunction "2_2") (pintype "passive"))
      (node (ref "R69") (pin "2") (pinfunction "2_2") (pintype "passive"))
      (node (ref "R71") (pin "1") (pinfunction "1_1") (pintype "passive"))
    )
    (net (code "42") (name "Net-(D33-A1)") (class "Default")
      (node (ref "D33") (pin "1") (pinfunction "A1_1") (pintype "passive"))
      (node (ref "Q5") (pin "2") (pinfunction "S_2") (pintype "passive"))
      (node (ref "R93") (pin "2") (pinfunction "2_2") (pintype "passive"))
    )
    (net (code "43") (name "Net-(D33-A2)") (class "Default")
      (node (ref "D33") (pin "2") (pinfunction "A2_2") (pintype "passive"))
      (node (ref "R96") (pin "1") (pinfunction "1_1") (pintype "passive"))
    )
    (net (code "44") (name "Net-(D33-K)") (class "Default")
      (node (ref "D33") (pin "3") (pinfunction "K_3") (pintype "passive"))
      (node (ref "Q5") (pin "3") (pinfunction "D_3") (pintype "passive"))
      (node (ref "R53") (pin "1") (pinfunction "1_1") (pintype "passive"))
    )
    (net (code "45") (name "Net-(FB1-Pad2)") (class "Default")
      (node (ref "FB1") (pin "2") (pinfunction "2_2") (pintype "passive"))
      (node (ref "R81") (pin "2") (pinfunction "2_2") (pintype "passive"))
    )
    (net (code "46") (name "Net-(FB2-Pad2)") (class "Default")
      (node (ref "FB2") (pin "2") (pinfunction "2_2") (pintype "passive"))
      (node (ref "R83") (pin "2") (pinfunction "2_2") (pintype "passive"))
    )
    (net (code "47") (name "Net-(FB3-Pad2)") (class "Default")
      (node (ref "FB3") (pin "2") (pinfunction "2_2") (pintype "passive"))
      (node (ref "R84") (pin "2") (pinfunction "2_2") (pintype "passive"))
    )
    (net (code "48") (name "Net-(FB4-Pad2)") (class "Default")
      (node (ref "FB4") (pin "2") (pinfunction "2_2") (pintype "passive"))
      (node (ref "R85") (pin "2") (pinfunction "2_2") (pintype "passive"))
    )
    (net (code "49") (name "Net-(FB5-Pad2)") (class "Default")
      (node (ref "FB5") (pin "2") (pinfunction "2_2") (pintype "passive"))
      (node (ref "R86") (pin "2") (pinfunction "2_2") (pintype "passive"))
    )
    (net (code "50") (name "Net-(FB6-Pad2)") (class "Default")
      (node (ref "FB6") (pin "2") (pinfunction "2_2") (pintype "passive"))
      (node (ref "R89") (pin "2") (pinfunction "2_2") (pintype "passive"))
    )
    (net (code "51") (name "Net-(FB7-Pad2)") (class "Default")
      (node (ref "FB7") (pin "2") (pinfunction "2_2") (pintype "passive"))
      (node (ref "R91") (pin "2") (pinfunction "2_2") (pintype "passive"))
    )
    (net (code "52") (name "Net-(FB8-Pad2)") (class "Default")
      (node (ref "FB8") (pin "2") (pinfunction "2_2") (pintype "passive"))
      (node (ref "R92") (pin "2") (pinfunction "2_2") (pintype "passive"))
    )
    (net (code "53") (name "Net-(Q1-G)") (class "Default")
      (node (ref "Q1") (pin "1") (pinfunction "G_1") (pintype "passive"))
      (node (ref "R69") (pin "1") (pinfunction "1_1") (pintype "passive"))
      (node (ref "R73") (pin "2") (pinfunction "2_2") (pintype "passive"))
    )
    (net (code "54") (name "Net-(Q2-D)") (class "Default")
      (node (ref "Q2") (pin "3") (pinfunction "D_3") (pintype "passive"))
      (node (ref "R80") (pin "1") (pinfunction "1_1") (pintype "passive"))
      (node (ref "R82") (pin "1") (pinfunction "1_1") (pintype "passive"))
    )
    (net (code "55") (name "Net-(Q3-S)") (class "Default")
      (node (ref "Q3") (pin "2") (pinfunction "S_2") (pintype "passive"))
      (node (ref "R88") (pin "1") (pinfunction "1_1") (pintype "passive"))
      (node (ref "R90") (pin "1") (pinfunction "1_1") (pintype "passive"))
    )
    (net (code "56") (name "Net-(Q4-D)") (class "Default")
      (node (ref "FB1") (pin "1") (pinfunction "1_1") (pintype "passive"))
      (node (ref "FB2") (pin "1") (pinfunction "1_1") (pintype "passive"))
      (node (ref "FB3") (pin "1") (pinfunction "1_1") (pintype "passive"))
      (node (ref "FB4") (pin "1") (pinfunction "1_1") (pintype "passive"))
      (node (ref "FB5") (pin "1") (pinfunction "1_1") (pintype "passive"))
      (node (ref "FB6") (pin "1") (pinfunction "1_1") (pintype "passive"))
      (node (ref "FB7") (pin "1") (pinfunction "1_1") (pintype "passive"))
      (node (ref "FB8") (pin "1") (pinfunction "1_1") (pintype "passive"))
      (node (ref "Q4") (pin "3") (pinfunction "D_3") (pintype "passive"))
    )
    (net (code "57") (name "Net-(U9-EN)") (class "Default")
      (node (ref "R28") (pin "2") (pinfunction "2_2") (pintype "passive"))
      (node (ref "U9") (pin "4") (pinfunction "EN_4") (pintype "input"))
    )
    (net (code "58") (name "Net-(U9-FLG)") (class "Default")
      (node (ref "C84") (pin "2") (pinfunction "2_2") (pintype "passive"))
      (node (ref "R28") (pin "1") (pinfunction "1_1") (pintype "passive"))
      (node (ref "R66") (pin "1") (pinfunction "1_1") (pintype "passive"))
      (node (ref "U9") (pin "3") (pinfunction "FLG_3") (pintype "output"))
    )
    (net (code "59") (name "Net-(U11-VIN)") (class "Default")
      (node (ref "C38") (pin "2") (pinfunction "2_2") (pintype "passive"))
      (node (ref "R55") (pin "2") (pinfunction "2_2") (pintype "passive"))
      (node (ref "U11") (pin "3") (pinfunction "VIN_3") (pintype "power_in"))
    )
    (net (code "60") (name "unconnected-(J6-Pad14)") (class "Default")
      (node (ref "J6") (pin "14") (pinfunction "14_14") (pintype "passive+no_connect"))
    )
    (net (code "61") (name "unconnected-(U8-FLG-Pad3)") (class "Default")
      (node (ref "U8") (pin "3") (pinfunction "FLG_3") (pintype "output+no_connect"))
    )
  )
)
